# ProProject_circuller_2023-10-12.net
KiCad netlist of a schematic drawn in EasyEDA Pro
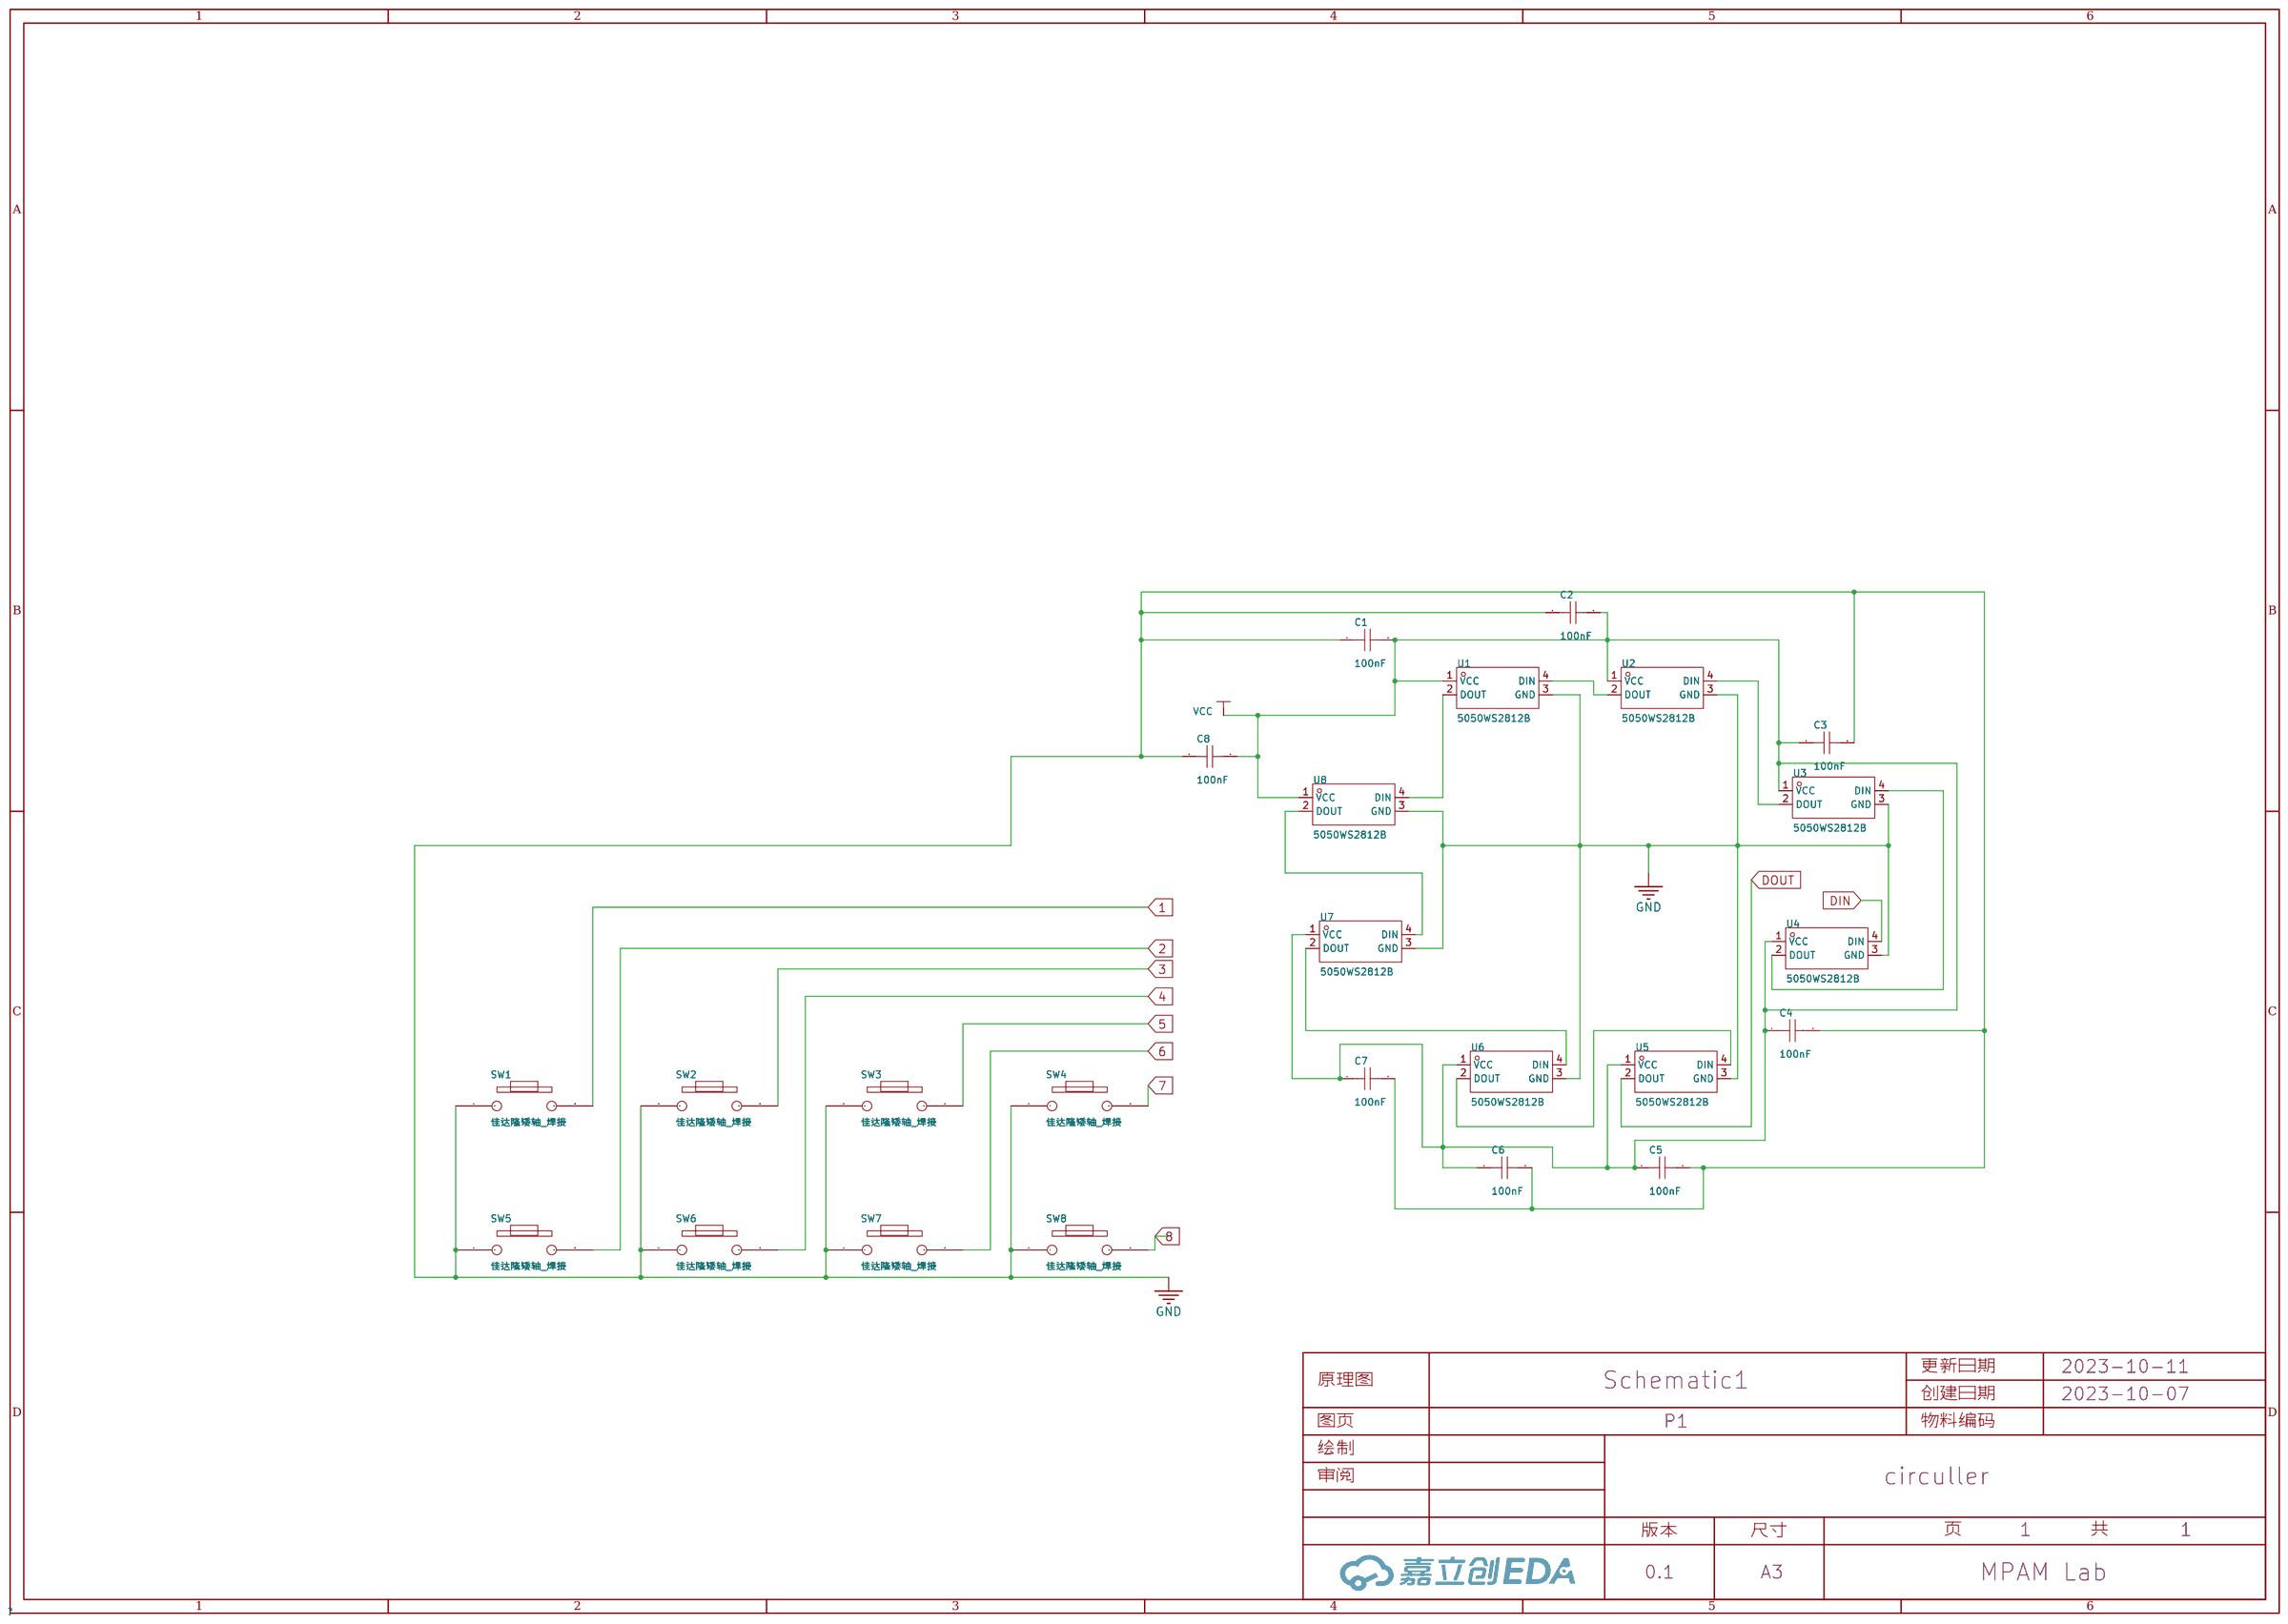
[diagram p0: schematic sheet]

(export (version "E")
  (design (tool "Eeschema 10.0.6"))
  (components
    (comp (ref "C1")
      (value "100nF")
      (footprint "easyedapro:C0603")
      (libsource (lib "easyedapro") (part "CapAcitance"))
    )
    (comp (ref "C2")
      (value "100nF")
      (footprint "easyedapro:C0603")
      (libsource (lib "easyedapro") (part "CapAcitance"))
    )
    (comp (ref "C3")
      (value "100nF")
      (footprint "easyedapro:C0603")
      (libsource (lib "easyedapro") (part "CapAcitance"))
    )
    (comp (ref "C4")
      (value "100nF")
      (footprint "easyedapro:C0603")
      (libsource (lib "easyedapro") (part "CapAcitance"))
    )
    (comp (ref "C5")
      (value "100nF")
      (footprint "easyedapro:C0603")
      (libsource (lib "easyedapro") (part "CapAcitance"))
    )
    (comp (ref "C6")
      (value "100nF")
      (footprint "easyedapro:C0603")
      (libsource (lib "easyedapro") (part "CapAcitance"))
    )
    (comp (ref "C7")
      (value "100nF")
      (footprint "easyedapro:C0603")
      (libsource (lib "easyedapro") (part "CapAcitance"))
    )
    (comp (ref "C8")
      (value "100nF")
      (footprint "easyedapro:C0603")
      (libsource (lib "easyedapro") (part "CapAcitance"))
    )
    (comp (ref "SW1") (value "佳达隆矮轴_焊接") (libsource (lib "easyedapro") (part "佳达隆矮轴_焊接")))
    (comp (ref "SW2") (value "佳达隆矮轴_焊接") (libsource (lib "easyedapro") (part "佳达隆矮轴_焊接")))
    (comp (ref "SW3") (value "佳达隆矮轴_焊接") (libsource (lib "easyedapro") (part "佳达隆矮轴_焊接")))
    (comp (ref "SW4") (value "佳达隆矮轴_焊接") (libsource (lib "easyedapro") (part "佳达隆矮轴_焊接")))
    (comp (ref "SW5") (value "佳达隆矮轴_焊接") (libsource (lib "easyedapro") (part "佳达隆矮轴_焊接")))
    (comp (ref "SW6") (value "佳达隆矮轴_焊接") (libsource (lib "easyedapro") (part "佳达隆矮轴_焊接")))
    (comp (ref "SW7") (value "佳达隆矮轴_焊接") (libsource (lib "easyedapro") (part "佳达隆矮轴_焊接")))
    (comp (ref "SW8") (value "佳达隆矮轴_焊接") (libsource (lib "easyedapro") (part "佳达隆矮轴_焊接")))
    (comp (ref "U1")
      (value "5050WS2812B")
      (footprint "easyedapro:LED-SMD_5050WS2812B")
      (libsource (lib "easyedapro") (part "5050WS2812B"))
    )
    (comp (ref "U2")
      (value "5050WS2812B")
      (footprint "easyedapro:LED-SMD_5050WS2812B")
      (libsource (lib "easyedapro") (part "5050WS2812B"))
    )
    (comp (ref "U3")
      (value "5050WS2812B")
      (footprint "easyedapro:LED-SMD_5050WS2812B")
      (libsource (lib "easyedapro") (part "5050WS2812B"))
    )
    (comp (ref "U4")
      (value "5050WS2812B")
      (footprint "easyedapro:LED-SMD_5050WS2812B")
      (libsource (lib "easyedapro") (part "5050WS2812B"))
    )
    (comp (ref "U5")
      (value "5050WS2812B")
      (footprint "easyedapro:LED-SMD_5050WS2812B")
      (libsource (lib "easyedapro") (part "5050WS2812B"))
    )
    (comp (ref "U6")
      (value "5050WS2812B")
      (footprint "easyedapro:LED-SMD_5050WS2812B")
      (libsource (lib "easyedapro") (part "5050WS2812B"))
    )
    (comp (ref "U7")
      (value "5050WS2812B")
      (footprint "easyedapro:LED-SMD_5050WS2812B")
      (libsource (lib "easyedapro") (part "5050WS2812B"))
    )
    (comp (ref "U8")
      (value "5050WS2812B")
      (footprint "easyedapro:LED-SMD_5050WS2812B")
      (libsource (lib "easyedapro") (part "5050WS2812B"))
    )
  )
  (nets
    (net (code "1") (name "1") (class "Default")
      (node (ref "SW1") (pin "2") (pinfunction "2_2") (pintype "input"))
    )
    (net (code "2") (name "2") (class "Default")
      (node (ref "SW5") (pin "2") (pinfunction "2_2") (pintype "input"))
    )
    (net (code "3") (name "3") (class "Default")
      (node (ref "SW2") (pin "2") (pinfunction "2_2") (pintype "input"))
    )
    (net (code "4") (name "4") (class "Default")
      (node (ref "SW6") (pin "2") (pinfunction "2_2") (pintype "input"))
    )
    (net (code "5") (name "5") (class "Default")
      (node (ref "SW3") (pin "2") (pinfunction "2_2") (pintype "input"))
    )
    (net (code "6") (name "6") (class "Default")
      (node (ref "SW7") (pin "2") (pinfunction "2_2") (pintype "input"))
    )
    (net (code "7") (name "7") (class "Default")
      (node (ref "SW4") (pin "2") (pinfunction "2_2") (pintype "input"))
    )
    (net (code "8") (name "8") (class "Default")
      (node (ref "SW8") (pin "2") (pinfunction "2_2") (pintype "input"))
    )
    (net (code "9") (name "DIN") (class "Default")
      (node (ref "U4") (pin "4") (pinfunction "DIN_4") (pintype "input"))
    )
    (net (code "10") (name "DOUT") (class "Default")
      (node (ref "U5") (pin "2") (pinfunction "DOUT_2") (pintype "input"))
    )
    (net (code "11") (name "GND") (class "Default")
      (node (ref "C1") (pin "1") (pinfunction "1_1") (pintype "input"))
      (node (ref "C2") (pin "1") (pinfunction "1_1") (pintype "input"))
      (node (ref "C3") (pin "2") (pinfunction "2_2") (pintype "input"))
      (node (ref "C4") (pin "2") (pinfunction "2_2") (pintype "input"))
      (node (ref "C5") (pin "2") (pinfunction "2_2") (pintype "input"))
      (node (ref "C6") (pin "2") (pinfunction "2_2") (pintype "input"))
      (node (ref "C7") (pin "2") (pinfunction "2_2") (pintype "input"))
      (node (ref "C8") (pin "1") (pinfunction "1_1") (pintype "input"))
      (node (ref "SW1") (pin "1") (pinfunction "1_1") (pintype "input"))
      (node (ref "SW2") (pin "1") (pinfunction "1_1") (pintype "input"))
      (node (ref "SW3") (pin "1") (pinfunction "1_1") (pintype "input"))
      (node (ref "SW4") (pin "1") (pinfunction "1_1") (pintype "input"))
      (node (ref "SW5") (pin "1") (pinfunction "1_1") (pintype "input"))
      (node (ref "SW6") (pin "1") (pinfunction "1_1") (pintype "input"))
      (node (ref "SW7") (pin "1") (pinfunction "1_1") (pintype "input"))
      (node (ref "SW8") (pin "1") (pinfunction "1_1") (pintype "input"))
      (node (ref "U1") (pin "3") (pinfunction "GND_3") (pintype "input"))
      (node (ref "U2") (pin "3") (pinfunction "GND_3") (pintype "input"))
      (node (ref "U3") (pin "3") (pinfunction "GND_3") (pintype "input"))
      (node (ref "U4") (pin "3") (pinfunction "GND_3") (pintype "input"))
      (node (ref "U5") (pin "3") (pinfunction "GND_3") (pintype "input"))
      (node (ref "U6") (pin "3") (pinfunction "GND_3") (pintype "input"))
      (node (ref "U7") (pin "3") (pinfunction "GND_3") (pintype "input"))
      (node (ref "U8") (pin "3") (pinfunction "GND_3") (pintype "input"))
    )
    (net (code "12") (name "Net-(U1-DIN)") (class "Default")
      (node (ref "U1") (pin "4") (pinfunction "DIN_4") (pintype "input"))
      (node (ref "U2") (pin "2") (pinfunction "DOUT_2") (pintype "input"))
    )
    (net (code "13") (name "Net-(U1-DOUT)") (class "Default")
      (node (ref "U1") (pin "2") (pinfunction "DOUT_2") (pintype "input"))
      (node (ref "U8") (pin "4") (pinfunction "DIN_4") (pintype "input"))
    )
    (net (code "14") (name "Net-(U2-DIN)") (class "Default")
      (node (ref "U2") (pin "4") (pinfunction "DIN_4") (pintype "input"))
      (node (ref "U3") (pin "2") (pinfunction "DOUT_2") (pintype "input"))
    )
    (net (code "15") (name "Net-(U3-DIN)") (class "Default")
      (node (ref "U3") (pin "4") (pinfunction "DIN_4") (pintype "input"))
      (node (ref "U4") (pin "2") (pinfunction "DOUT_2") (pintype "input"))
    )
    (net (code "16") (name "Net-(U5-DIN)") (class "Default")
      (node (ref "U5") (pin "4") (pinfunction "DIN_4") (pintype "input"))
      (node (ref "U6") (pin "2") (pinfunction "DOUT_2") (pintype "input"))
    )
    (net (code "17") (name "Net-(U6-DIN)") (class "Default")
      (node (ref "U6") (pin "4") (pinfunction "DIN_4") (pintype "input"))
      (node (ref "U7") (pin "2") (pinfunction "DOUT_2") (pintype "input"))
    )
    (net (code "18") (name "Net-(U7-DIN)") (class "Default")
      (node (ref "U7") (pin "4") (pinfunction "DIN_4") (pintype "input"))
      (node (ref "U8") (pin "2") (pinfunction "DOUT_2") (pintype "input"))
    )
    (net (code "19") (name "VCC") (class "Default")
      (node (ref "C1") (pin "2") (pinfunction "2_2") (pintype "input"))
      (node (ref "C2") (pin "2") (pinfunction "2_2") (pintype "input"))
      (node (ref "C3") (pin "1") (pinfunction "1_1") (pintype "input"))
      (node (ref "C4") (pin "1") (pinfunction "1_1") (pintype "input"))
      (node (ref "C5") (pin "1") (pinfunction "1_1") (pintype "input"))
      (node (ref "C6") (pin "1") (pinfunction "1_1") (pintype "input"))
      (node (ref "C7") (pin "1") (pinfunction "1_1") (pintype "input"))
      (node (ref "C8") (pin "2") (pinfunction "2_2") (pintype "input"))
      (node (ref "U1") (pin "1") (pinfunction "VCC_1") (pintype "input"))
      (node (ref "U2") (pin "1") (pinfunction "VCC_1") (pintype "input"))
      (node (ref "U3") (pin "1") (pinfunction "VCC_1") (pintype "input"))
      (node (ref "U4") (pin "1") (pinfunction "VCC_1") (pintype "input"))
      (node (ref "U5") (pin "1") (pinfunction "VCC_1") (pintype "input"))
      (node (ref "U6") (pin "1") (pinfunction "VCC_1") (pintype "input"))
      (node (ref "U7") (pin "1") (pinfunction "VCC_1") (pintype "input"))
      (node (ref "U8") (pin "1") (pinfunction "VCC_1") (pintype "input"))
    )
  )
)
